# 3_Shutdown.net
KiCad netlist of a schematic drawn in Altium Designer
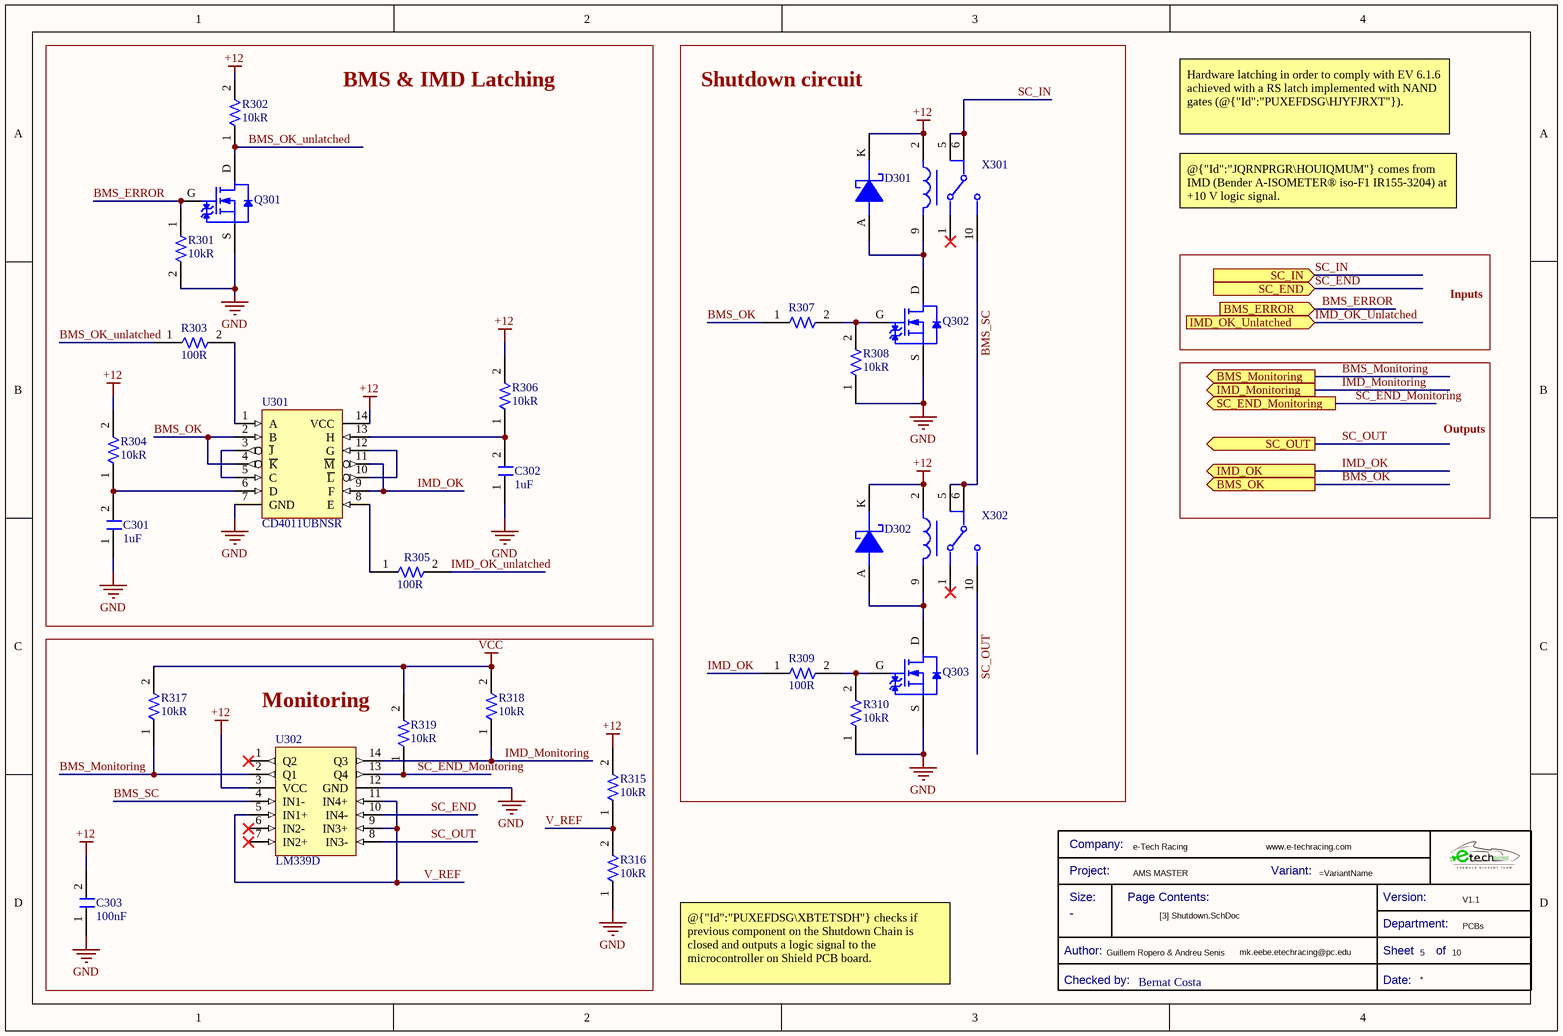
[diagram p0: [3] Shutdown.SchDoc]

(export (version "E")
  (design (tool "Eeschema 10.0.6"))
  (components
    (comp (ref "C301")
      (value "885012207103")
      (footprint "C0805FNPC-R")
      (fields
        (field (name "TOLERANCE") "10%")
        (field (name "CAPACITANCE") "1uF")
        (field (name ".CREATOR") "GP")
      )
      (libsource (lib "Passives") (part "C1u-50V-0805FNPC-X7R"))
    )
    (comp (ref "C302")
      (value "885012207103")
      (footprint "C0805FNPC-R")
      (fields
        (field (name "TOLERANCE") "10%")
        (field (name "CAPACITANCE") "1uF")
        (field (name ".CREATOR") "GP")
      )
      (libsource (lib "Passives") (part "C1u-50V-0805FNPC-X7R"))
    )
    (comp (ref "C303")
      (value "885012207098")
      (footprint "C0805FNPC-R")
      (description "Cap, 0.1ΜF, 50V, 10%, X7R, 0805")
      (fields
        (field (name "TOLERANCE") "10%")
        (field (name "CAPACITANCE") "100nF")
        (field (name ".CREATOR") "DR")
      )
      (libsource (lib "Passives") (part "C100n-50V-0805FNPC-X7R"))
    )
    (comp (ref "D301")
      (value "MBR0530")
      (footprint "DSC-SOD123")
      (description "VR=30V IF=500mA 30pF P=410mW")
      (fields (field (name ".CREATOR") "GP"))
      (libsource (lib "Filter components") (part "DSC-0.5/30-SOD123"))
    )
    (comp (ref "D302")
      (value "MBR0530")
      (footprint "DSC-SOD123")
      (description "VR=30V IF=500mA 30pF P=410mW")
      (fields (field (name ".CREATOR") "GP"))
      (libsource (lib "Filter components") (part "DSC-0.5/30-SOD123"))
    )
    (comp (ref "Q301")
      (value "CPH3455-TL-H")
      (footprint "TRT-NCH-3/35-CPH")
      (description "CPH3455-TL-H N-channel MOSFET Transistor; 3 A; 35 V; 3-Pin CPH")
      (fields (field (name "MANUFACTURER") "ON Semiconductor") (field (name ".CREATOR") "GP"))
      (libsource (lib "Semiconductor") (part "TRT-NCH-3/35-CPH"))
    )
    (comp (ref "Q302")
      (value "CPH3455-TL-H")
      (footprint "TRT-NCH-3/35-CPH")
      (description "CPH3455-TL-H N-channel MOSFET Transistor; 3 A; 35 V; 3-Pin CPH")
      (fields (field (name "MANUFACTURER") "ON Semiconductor") (field (name ".CREATOR") "GP"))
      (libsource (lib "Semiconductor") (part "TRT-NCH-3/35-CPH"))
    )
    (comp (ref "Q303")
      (value "CPH3455-TL-H")
      (footprint "TRT-NCH-3/35-CPH")
      (description "CPH3455-TL-H N-channel MOSFET Transistor; 3 A; 35 V; 3-Pin CPH")
      (fields (field (name "MANUFACTURER") "ON Semiconductor") (field (name ".CREATOR") "GP"))
      (libsource (lib "Semiconductor") (part "TRT-NCH-3/35-CPH"))
    )
    (comp (ref "R301")
      (value "CR0805-JW-103ELF")
      (footprint "R0805FTK")
      (fields
        (field (name "TOLERANCE") "5%")
        (field (name "RESISTANCE") "10kR")
        (field (name ".CREATOR") "DR")
      )
      (libsource (lib "Passives") (part "R10k-0805FTK"))
    )
    (comp (ref "R302")
      (value "CR0805-JW-103ELF")
      (footprint "R0805FTK")
      (fields
        (field (name "TOLERANCE") "5%")
        (field (name "RESISTANCE") "10kR")
        (field (name ".CREATOR") "DR")
      )
      (libsource (lib "Passives") (part "R10k-0805FTK"))
    )
    (comp (ref "R303")
      (value "CR0805-FX-1000ELF")
      (footprint "R0805FTK")
      (description "Res Thick Film 0805 100 Ohm 1% 1/8W ±100ppm/°C Molded SMD SMD Paper Tape on Plastic Reel")
      (fields
        (field (name "TOLERANCE") "1%")
        (field (name "RESISTANCE") "100R")
        (field (name ".CREATOR") "DR")
      )
      (libsource (lib "Passives") (part "R100-0805FTK"))
    )
    (comp (ref "R304")
      (value "CR0805-JW-103ELF")
      (footprint "R0805FTK")
      (fields
        (field (name "TOLERANCE") "5%")
        (field (name "RESISTANCE") "10kR")
        (field (name ".CREATOR") "DR")
      )
      (libsource (lib "Passives") (part "R10k-0805FTK"))
    )
    (comp (ref "R305")
      (value "CR0805-FX-1000ELF")
      (footprint "R0805FTK")
      (description "Res Thick Film 0805 100 Ohm 1% 1/8W ±100ppm/°C Molded SMD SMD Paper Tape on Plastic Reel")
      (fields
        (field (name "TOLERANCE") "1%")
        (field (name "RESISTANCE") "100R")
        (field (name ".CREATOR") "DR")
      )
      (libsource (lib "Passives") (part "R100-0805FTK"))
    )
    (comp (ref "R306")
      (value "CR0805-JW-103ELF")
      (footprint "R0805FTK")
      (fields
        (field (name "TOLERANCE") "5%")
        (field (name "RESISTANCE") "10kR")
        (field (name ".CREATOR") "DR")
      )
      (libsource (lib "Passives") (part "R10k-0805FTK"))
    )
    (comp (ref "R307")
      (value "CR0805-FX-1000ELF")
      (footprint "R0805FTK")
      (description "Res Thick Film 0805 100 Ohm 1% 1/8W ±100ppm/°C Molded SMD SMD Paper Tape on Plastic Reel")
      (fields (field (name "TOLERANCE") "1%") (field (name ".CREATOR") "DR"))
      (libsource (lib "Passives") (part "R100-0805FTK"))
    )
    (comp (ref "R308")
      (value "CR0805-JW-103ELF")
      (footprint "R0805FTK")
      (fields
        (field (name "TOLERANCE") "5%")
        (field (name "RESISTANCE") "10kR")
        (field (name ".CREATOR") "DR")
      )
      (libsource (lib "Passives") (part "R10k-0805FTK"))
    )
    (comp (ref "R309")
      (value "CR0805-FX-1000ELF")
      (footprint "R0805FTK")
      (description "Res Thick Film 0805 100 Ohm 1% 1/8W ±100ppm/°C Molded SMD SMD Paper Tape on Plastic Reel")
      (fields
        (field (name "TOLERANCE") "1%")
        (field (name "RESISTANCE") "100R")
        (field (name ".CREATOR") "DR")
      )
      (libsource (lib "Passives") (part "R100-0805FTK"))
    )
    (comp (ref "R310")
      (value "CR0805-JW-103ELF")
      (footprint "R0805FTK")
      (fields
        (field (name "TOLERANCE") "5%")
        (field (name "RESISTANCE") "10kR")
        (field (name ".CREATOR") "DR")
      )
      (libsource (lib "Passives") (part "R10k-0805FTK"))
    )
    (comp (ref "R315")
      (value "CR0805-JW-103ELF")
      (footprint "R0805FTK")
      (fields
        (field (name "TOLERANCE") "5%")
        (field (name "RESISTANCE") "10kR")
        (field (name ".CREATOR") "DR")
      )
      (libsource (lib "Passives") (part "R10k-0805FTK"))
    )
    (comp (ref "R316")
      (value "CR0805-JW-103ELF")
      (footprint "R0805FTK")
      (fields
        (field (name "TOLERANCE") "5%")
        (field (name "RESISTANCE") "10kR")
        (field (name ".CREATOR") "DR")
      )
      (libsource (lib "Passives") (part "R10k-0805FTK"))
    )
    (comp (ref "R317")
      (value "CR0805-JW-103ELF")
      (footprint "R0805FTK")
      (fields
        (field (name "TOLERANCE") "5%")
        (field (name "RESISTANCE") "10kR")
        (field (name ".CREATOR") "DR")
      )
      (libsource (lib "Passives") (part "R10k-0805FTK"))
    )
    (comp (ref "R318")
      (value "CR0805-JW-103ELF")
      (footprint "R0805FTK")
      (fields
        (field (name "TOLERANCE") "5%")
        (field (name "RESISTANCE") "10kR")
        (field (name ".CREATOR") "DR")
      )
      (libsource (lib "Passives") (part "R10k-0805FTK"))
    )
    (comp (ref "R319")
      (value "CR0805-JW-103ELF")
      (footprint "R0805FTK")
      (fields
        (field (name "TOLERANCE") "5%")
        (field (name "RESISTANCE") "10kR")
        (field (name ".CREATOR") "DR")
      )
      (libsource (lib "Passives") (part "R10k-0805FTK"))
    )
    (comp (ref "U301")
      (value "CD4011UBSNR")
      (footprint "ARRAY_4_NAND")
      (description "CD4011UB Cmos Quad 2-INPUT Nand")
      (fields
        (field (name "MANUFACTURER") "Texas Instruments")
        (field (name "MANUFACTURER PART NUMBER") "CD4011UBNSR")
        (field (name ".CREATOR") "DO")
      )
      (libsource (lib "Integrated circuits") (part "Array_4_NAND"))
    )
    (comp (ref "U302")
      (value "LM339D")
      (footprint "Array_4_Amp_LM339D")
      (description "Comparator Quad ±18V/36V 14-Pin SOIC Tube")
      (fields
        (field (name "MANUFACTURER") "Texas Instruments")
        (field (name "MANUFACTURER PART NUMBER") "LM339D")
        (field (name ".CREATOR") "DO")
      )
      (libsource (lib "Integrated circuits") (part "Array_4_Amp_LM339D"))
    )
    (comp (ref "X301")
      (value "G5V-1-DC5")
      (footprint "Relay_G5V-1-DC5")
      (description "Electromechanical Relay SPDT 1A 5VDC 167Ohm Through Hole")
      (fields (field (name "MANUFACTURER") "Omron") (field (name ".CREATOR") "DO"))
      (libsource (lib "Electromechanical") (part "Relay_G5V-1-DC5"))
    )
    (comp (ref "X302")
      (value "G5V-1-DC5")
      (footprint "Relay_G5V-1-DC5")
      (description "Electromechanical Relay SPDT 1A 5VDC 167Ohm Through Hole")
      (fields (field (name "MANUFACTURER") "Omron") (field (name ".CREATOR") "DO"))
      (libsource (lib "Electromechanical") (part "Relay_G5V-1-DC5"))
    )
  )
  (nets
    (net (code "1") (name "+12") (class "Default")
      (node (ref "C303") (pin "2") (pinfunction "2_2") (pintype "passive"))
      (node (ref "D301") (pin "K") (pinfunction "K_K") (pintype "passive"))
      (node (ref "D302") (pin "K") (pinfunction "K_K") (pintype "passive"))
      (node (ref "R302") (pin "2") (pinfunction "2_2") (pintype "passive"))
      (node (ref "R304") (pin "2") (pinfunction "2_2") (pintype "passive"))
      (node (ref "R306") (pin "2") (pinfunction "2_2") (pintype "passive"))
      (node (ref "R315") (pin "2") (pinfunction "2_2") (pintype "passive"))
      (node (ref "U301") (pin "14") (pinfunction "VCC_14") (pintype "power_in"))
      (node (ref "U302") (pin "3") (pinfunction "VCC_3") (pintype "power_in"))
      (node (ref "X301") (pin "2") (pinfunction "2_2") (pintype "passive"))
      (node (ref "X302") (pin "2") (pinfunction "2_2") (pintype "passive"))
    )
    (net (code "2") (name "/BMS_ERROR") (class "Default")
      (node (ref "Q301") (pin "G") (pinfunction "G_G") (pintype "passive"))
      (node (ref "R301") (pin "1") (pinfunction "1_1") (pintype "passive"))
    )
    (net (code "3") (name "/BMS_Monitoring") (class "Default")
      (node (ref "R317") (pin "1") (pinfunction "1_1") (pintype "passive"))
      (node (ref "U302") (pin "2") (pinfunction "Q1_2") (pintype "output"))
    )
    (net (code "4") (name "/BMS_OK") (class "Default")
      (node (ref "R307") (pin "1") (pinfunction "1_1") (pintype "passive"))
      (node (ref "U301") (pin "2") (pinfunction "B_2") (pintype "input"))
      (node (ref "U301") (pin "4") (pinfunction "~{K}_4") (pintype "output"))
    )
    (net (code "5") (name "/BMS_OK_unlatched") (class "Default")
      (node (ref "Q301") (pin "D") (pinfunction "D_D") (pintype "passive"))
      (node (ref "R302") (pin "1") (pinfunction "1_1") (pintype "passive"))
      (node (ref "R303") (pin "1") (pinfunction "1_1") (pintype "passive"))
    )
    (net (code "6") (name "/BMS_SC") (class "Default")
      (node (ref "U302") (pin "4") (pinfunction "IN1-_4") (pintype "input"))
      (node (ref "X301") (pin "10") (pinfunction "10_10") (pintype "passive"))
      (node (ref "X302") (pin "5") (pinfunction "5_5") (pintype "passive"))
      (node (ref "X302") (pin "6") (pinfunction "6_6") (pintype "passive"))
    )
    (net (code "7") (name "/IMD_Monitoring") (class "Default")
      (node (ref "R318") (pin "1") (pinfunction "1_1") (pintype "passive"))
      (node (ref "U302") (pin "14") (pinfunction "Q3_14") (pintype "output"))
    )
    (net (code "8") (name "/IMD_OK") (class "Default")
      (node (ref "R309") (pin "1") (pinfunction "1_1") (pintype "passive"))
      (node (ref "U301") (pin "11") (pinfunction "~{M}_11") (pintype "output"))
      (node (ref "U301") (pin "9") (pinfunction "F_9") (pintype "input"))
    )
    (net (code "10") (name "/IMD_OK_unlatched") (class "Default")
      (node (ref "R305") (pin "2") (pinfunction "2_2") (pintype "passive"))
    )
    (net (code "11") (name "/SC_END") (class "Default")
      (node (ref "U302") (pin "10") (pinfunction "IN4-_10") (pintype "input"))
    )
    (net (code "12") (name "/SC_END_Monitoring") (class "Default")
      (node (ref "R319") (pin "1") (pinfunction "1_1") (pintype "passive"))
      (node (ref "U302") (pin "13") (pinfunction "Q4_13") (pintype "output"))
    )
    (net (code "13") (name "/SC_IN") (class "Default")
      (node (ref "X301") (pin "5") (pinfunction "5_5") (pintype "passive"))
      (node (ref "X301") (pin "6") (pinfunction "6_6") (pintype "passive"))
    )
    (net (code "14") (name "/SC_OUT") (class "Default")
      (node (ref "U302") (pin "8") (pinfunction "IN3-_8") (pintype "input"))
      (node (ref "X302") (pin "10") (pinfunction "10_10") (pintype "passive"))
    )
    (net (code "15") (name "/V_REF") (class "Default")
      (node (ref "R315") (pin "1") (pinfunction "1_1") (pintype "passive"))
      (node (ref "R316") (pin "2") (pinfunction "2_2") (pintype "passive"))
      (node (ref "U302") (pin "11") (pinfunction "IN4+_11") (pintype "input"))
      (node (ref "U302") (pin "5") (pinfunction "IN1+_5") (pintype "input"))
      (node (ref "U302") (pin "9") (pinfunction "IN3+_9") (pintype "input"))
    )
    (net (code "16") (name "GND") (class "Default")
      (node (ref "C301") (pin "1") (pinfunction "1_1") (pintype "passive"))
      (node (ref "C302") (pin "1") (pinfunction "1_1") (pintype "passive"))
      (node (ref "C303") (pin "1") (pinfunction "1_1") (pintype "passive"))
      (node (ref "Q301") (pin "S") (pinfunction "S_S") (pintype "passive"))
      (node (ref "Q302") (pin "S") (pinfunction "S_S") (pintype "passive"))
      (node (ref "Q303") (pin "S") (pinfunction "S_S") (pintype "passive"))
      (node (ref "R301") (pin "2") (pinfunction "2_2") (pintype "passive"))
      (node (ref "R308") (pin "1") (pinfunction "1_1") (pintype "passive"))
      (node (ref "R310") (pin "1") (pinfunction "1_1") (pintype "passive"))
      (node (ref "R316") (pin "1") (pinfunction "1_1") (pintype "passive"))
      (node (ref "U301") (pin "7") (pinfunction "GND_7") (pintype "power_in"))
      (node (ref "U302") (pin "12") (pinfunction "GND_12") (pintype "power_in"))
    )
    (net (code "17") (name "Net-(D301-PadA)") (class "Default")
      (node (ref "D301") (pin "A") (pinfunction "A_A") (pintype "passive"))
      (node (ref "Q302") (pin "D") (pinfunction "D_D") (pintype "passive"))
      (node (ref "X301") (pin "9") (pinfunction "9_9") (pintype "passive"))
    )
    (net (code "18") (name "Net-(D302-PadA)") (class "Default")
      (node (ref "D302") (pin "A") (pinfunction "A_A") (pintype "passive"))
      (node (ref "Q303") (pin "D") (pinfunction "D_D") (pintype "passive"))
      (node (ref "X302") (pin "9") (pinfunction "9_9") (pintype "passive"))
    )
    (net (code "19") (name "Net-(Q302-PadG)") (class "Default")
      (node (ref "Q302") (pin "G") (pinfunction "G_G") (pintype "passive"))
      (node (ref "R307") (pin "2") (pinfunction "2_2") (pintype "passive"))
      (node (ref "R308") (pin "2") (pinfunction "2_2") (pintype "passive"))
    )
    (net (code "20") (name "Net-(Q303-PadG)") (class "Default")
      (node (ref "Q303") (pin "G") (pinfunction "G_G") (pintype "passive"))
      (node (ref "R309") (pin "2") (pinfunction "2_2") (pintype "passive"))
      (node (ref "R310") (pin "2") (pinfunction "2_2") (pintype "passive"))
    )
    (net (code "21") (name "Net-(U301-A)") (class "Default")
      (node (ref "R303") (pin "2") (pinfunction "2_2") (pintype "passive"))
      (node (ref "U301") (pin "1") (pinfunction "A_1") (pintype "input"))
    )
    (net (code "22") (name "Net-(U301-C)") (class "Default")
      (node (ref "U301") (pin "3") (pinfunction "~{J}_3") (pintype "output"))
      (node (ref "U301") (pin "5") (pinfunction "C_5") (pintype "input"))
    )
    (net (code "23") (name "Net-(U301-D)") (class "Default")
      (node (ref "C301") (pin "2") (pinfunction "2_2") (pintype "passive"))
      (node (ref "R304") (pin "1") (pinfunction "1_1") (pintype "passive"))
      (node (ref "U301") (pin "6") (pinfunction "D_6") (pintype "input"))
    )
    (net (code "24") (name "Net-(U301-E)") (class "Default")
      (node (ref "R305") (pin "1") (pinfunction "1_1") (pintype "passive"))
      (node (ref "U301") (pin "8") (pinfunction "E_8") (pintype "input"))
    )
    (net (code "25") (name "Net-(U301-G)") (class "Default")
      (node (ref "U301") (pin "10") (pinfunction "~{L}_10") (pintype "output"))
      (node (ref "U301") (pin "12") (pinfunction "G_12") (pintype "input"))
    )
    (net (code "26") (name "Net-(U301-H)") (class "Default")
      (node (ref "C302") (pin "2") (pinfunction "2_2") (pintype "passive"))
      (node (ref "R306") (pin "1") (pinfunction "1_1") (pintype "passive"))
      (node (ref "U301") (pin "13") (pinfunction "H_13") (pintype "input"))
    )
    (net (code "27") (name "VCC") (class "Default")
      (node (ref "R317") (pin "2") (pinfunction "2_2") (pintype "passive"))
      (node (ref "R318") (pin "2") (pinfunction "2_2") (pintype "passive"))
      (node (ref "R319") (pin "2") (pinfunction "2_2") (pintype "passive"))
    )
    (net (code "28") (name "unconnected-(U302-IN2+-Pad7)") (class "Default")
      (node (ref "U302") (pin "7") (pinfunction "IN2+_7") (pintype "input+no_connect"))
    )
    (net (code "29") (name "unconnected-(U302-IN2--Pad6)") (class "Default")
      (node (ref "U302") (pin "6") (pinfunction "IN2-_6") (pintype "input+no_connect"))
    )
    (net (code "30") (name "unconnected-(U302-Q2-Pad1)") (class "Default")
      (node (ref "U302") (pin "1") (pinfunction "Q2_1") (pintype "output+no_connect"))
    )
    (net (code "31") (name "unconnected-(X301-Pad1)") (class "Default")
      (node (ref "X301") (pin "1") (pinfunction "1_1") (pintype "passive+no_connect"))
    )
    (net (code "32") (name "unconnected-(X302-Pad1)") (class "Default")
      (node (ref "X302") (pin "1") (pinfunction "1_1") (pintype "passive+no_connect"))
    )
  )
)
